# LT3045_mini_module.net
KiCad netlist of a schematic drawn in EAGLE
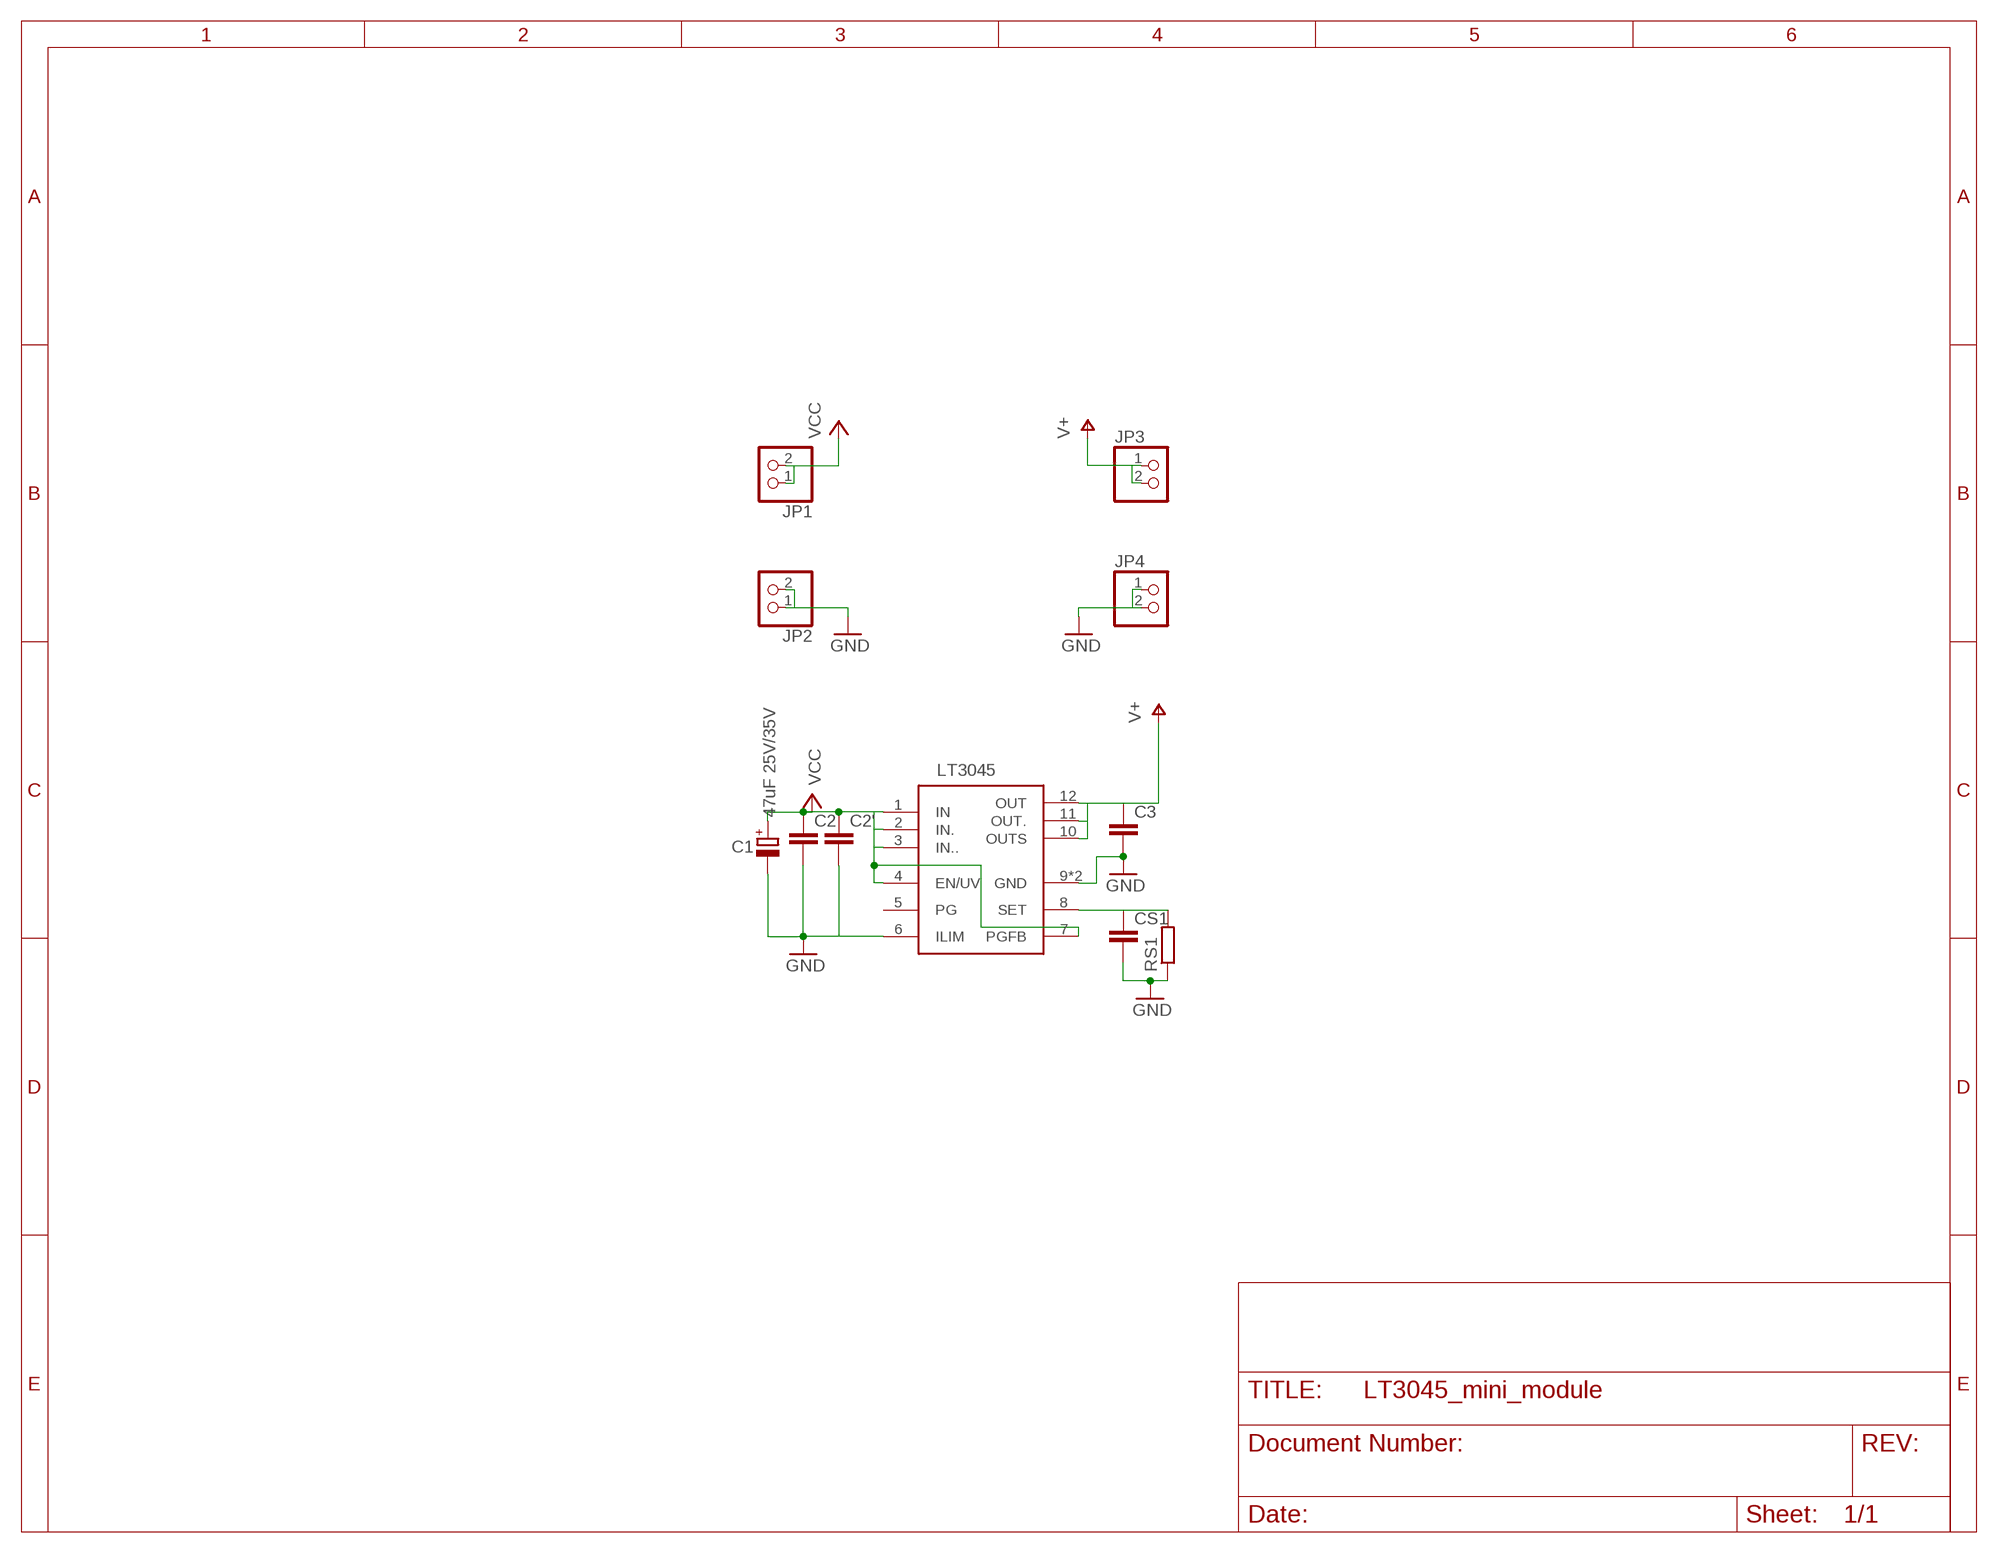
[diagram p0: schematic, sheet 1]

(export (version "E")
  (design (tool "Eeschema 10.0.6"))
  (components
    (comp (ref "C1")
      (value "47uF 25V/35V")
      (footprint "eagle-import:D_7343-31R")
      (libsource (lib "eagle-import") (part "CPOL-EUD/7343-31R"))
    )
    (comp (ref "C2")
      (value "C-EUC1206")
      (footprint "eagle-import:C1206")
      (libsource (lib "eagle-import") (part "C-EUC1206"))
    )
    (comp (ref "C2'")
      (value "C-EUC1206")
      (footprint "eagle-import:C1206")
      (libsource (lib "eagle-import") (part "C-EUC1206"))
    )
    (comp (ref "C3")
      (value "C-EUC1206")
      (footprint "eagle-import:C1206")
      (libsource (lib "eagle-import") (part "C-EUC1206"))
    )
    (comp (ref "CS1")
      (value "C-EUC1206")
      (footprint "eagle-import:C1206")
      (libsource (lib "eagle-import") (part "C-EUC1206"))
    )
    (comp (ref "JP1")
      (value "PINHD-1X2")
      (footprint "eagle-import:1X02")
      (libsource (lib "eagle-import") (part "PINHD-1X2"))
    )
    (comp (ref "JP2")
      (value "PINHD-1X2")
      (footprint "eagle-import:1X02")
      (libsource (lib "eagle-import") (part "PINHD-1X2"))
    )
    (comp (ref "JP3")
      (value "PINHD-1X2")
      (footprint "eagle-import:1X02")
      (libsource (lib "eagle-import") (part "PINHD-1X2"))
    )
    (comp (ref "JP4")
      (value "PINHD-1X2")
      (footprint "eagle-import:1X02")
      (libsource (lib "eagle-import") (part "PINHD-1X2"))
    )
    (comp (ref "RS1")
      (value "R-EU_R1206")
      (footprint "eagle-import:R1206")
      (libsource (lib "eagle-import") (part "R-EU_R1206"))
    )
    (comp (ref "U1")
      (value "LT3045")
      (footprint "eagle-import:MSOP12")
      (libsource (lib "eagle-import") (part "LT3045"))
    )
  )
  (nets
    (net (code "1") (name "GND") (class "Default")
      (node (ref "C1") (pin "-") (pinfunction "-_-") (pintype "passive"))
      (node (ref "C2") (pin "2") (pinfunction "2_2") (pintype "passive"))
      (node (ref "C2'") (pin "2") (pinfunction "2_2") (pintype "passive"))
      (node (ref "C3") (pin "2") (pinfunction "2_2") (pintype "passive"))
      (node (ref "CS1") (pin "2") (pinfunction "2_2") (pintype "passive"))
      (node (ref "JP2") (pin "1") (pinfunction "1_1") (pintype "passive"))
      (node (ref "JP2") (pin "2") (pinfunction "2_2") (pintype "passive"))
      (node (ref "JP4") (pin "1") (pinfunction "1_1") (pintype "passive"))
      (node (ref "JP4") (pin "2") (pinfunction "2_2") (pintype "passive"))
      (node (ref "RS1") (pin "1") (pinfunction "1_1") (pintype "passive"))
      (node (ref "U1") (pin "6") (pinfunction "ILIM_6") (pintype "bidirectional"))
      (node (ref "U1") (pin "9") (pinfunction "GND_9") (pintype "bidirectional"))
      (node (ref "U1") (pin "EXP") (pinfunction "GND_EXP") (pintype "bidirectional"))
    )
    (net (code "2") (name "Net-(U1-SET)") (class "Default")
      (node (ref "CS1") (pin "1") (pinfunction "1_1") (pintype "passive"))
      (node (ref "RS1") (pin "2") (pinfunction "2_2") (pintype "passive"))
      (node (ref "U1") (pin "8") (pinfunction "SET_8") (pintype "bidirectional"))
    )
    (net (code "3") (name "V+") (class "Default")
      (node (ref "C3") (pin "1") (pinfunction "1_1") (pintype "passive"))
      (node (ref "JP3") (pin "1") (pinfunction "1_1") (pintype "passive"))
      (node (ref "JP3") (pin "2") (pinfunction "2_2") (pintype "passive"))
      (node (ref "U1") (pin "10") (pinfunction "OUTS_10") (pintype "bidirectional"))
      (node (ref "U1") (pin "11") (pinfunction "OUT._11") (pintype "bidirectional"))
      (node (ref "U1") (pin "12") (pinfunction "OUT_12") (pintype "bidirectional"))
    )
    (net (code "4") (name "VCC") (class "Default")
      (node (ref "C1") (pin "+") (pinfunction "+_+") (pintype "passive"))
      (node (ref "C2") (pin "1") (pinfunction "1_1") (pintype "passive"))
      (node (ref "C2'") (pin "1") (pinfunction "1_1") (pintype "passive"))
      (node (ref "JP1") (pin "1") (pinfunction "1_1") (pintype "passive"))
      (node (ref "JP1") (pin "2") (pinfunction "2_2") (pintype "passive"))
      (node (ref "U1") (pin "1") (pinfunction "IN_1") (pintype "bidirectional"))
      (node (ref "U1") (pin "2") (pinfunction "IN._2") (pintype "bidirectional"))
      (node (ref "U1") (pin "3") (pinfunction "IN.._3") (pintype "bidirectional"))
      (node (ref "U1") (pin "4") (pinfunction "EN/UV_4") (pintype "bidirectional"))
      (node (ref "U1") (pin "7") (pinfunction "PGFB_7") (pintype "bidirectional"))
    )
    (net (code "5") (name "unconnected-(U1-PG-Pad5)") (class "Default")
      (node (ref "U1") (pin "5") (pinfunction "PG_5") (pintype "bidirectional"))
    )
  )
)
